# RGB_LED.net
KiCad netlist of a schematic drawn in Altium Designer
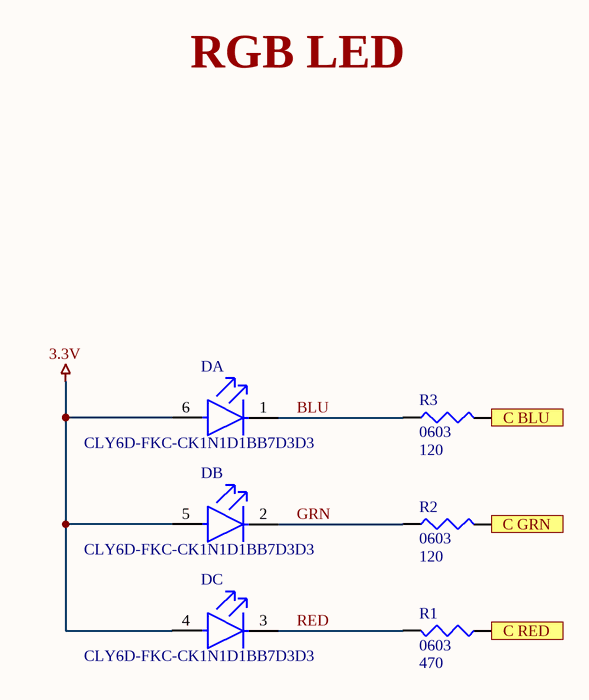
[diagram p0: RGB LED.SchDoc]

(export (version "E")
  (design (tool "Eeschema 10.0.6"))
  (components
    (comp (ref "D")
      (value "CLY6D-FKC-CK1N1D1BB7D3D3")
      (footprint "FP-CLY6D-FKC-MFG")
      (description "LED RGB DIFFUSED 6PLCC SMD")
      (libsource (lib "Altium Content Vault") (part "675964bc96c2f6a68928e7004de3fc3"))
    )
    (comp (ref "R1")
      (value "0603")
      (footprint "J1-0603")
      (description "Resistor")
      (fields (field (name "ALTIUM_VALUE") "470") (field (name "PUBLISHER") "Altium Limited"))
      (libsource (lib "Miscellaneous Devices") (part "Res3"))
    )
    (comp (ref "R2")
      (value "0603")
      (footprint "J1-0603")
      (description "Resistor")
      (fields (field (name "ALTIUM_VALUE") "120") (field (name "PUBLISHER") "Altium Limited"))
      (libsource (lib "Miscellaneous Devices") (part "Res3"))
    )
    (comp (ref "R3")
      (value "0603")
      (footprint "J1-0603")
      (description "Resistor")
      (fields (field (name "ALTIUM_VALUE") "120") (field (name "PUBLISHER") "Altium Limited"))
      (libsource (lib "Miscellaneous Devices") (part "Res3"))
    )
  )
  (nets
    (net (code "1") (name "/BLU") (class "Default")
      (node (ref "D") (pin "1") (pinfunction "BLUE(C)_1") (pintype "passive"))
      (node (ref "R3") (pin "1") (pinfunction "1_1") (pintype "passive"))
    )
    (net (code "2") (name "/C BLU") (class "Default")
      (node (ref "R3") (pin "2") (pinfunction "2_2") (pintype "passive"))
    )
    (net (code "3") (name "/C GRN") (class "Default")
      (node (ref "R2") (pin "2") (pinfunction "2_2") (pintype "passive"))
    )
    (net (code "4") (name "/C RED") (class "Default")
      (node (ref "R1") (pin "1") (pinfunction "1_1") (pintype "passive"))
    )
    (net (code "5") (name "/GRN") (class "Default")
      (node (ref "D") (pin "2") (pinfunction "GREEN(C)_2") (pintype "passive"))
      (node (ref "R2") (pin "1") (pinfunction "1_1") (pintype "passive"))
    )
    (net (code "6") (name "/RED") (class "Default")
      (node (ref "D") (pin "3") (pinfunction "RED(C)_3") (pintype "passive"))
      (node (ref "R1") (pin "2") (pinfunction "2_2") (pintype "passive"))
    )
    (net (code "7") (name "3.3V") (class "Default")
      (node (ref "D") (pin "4") (pinfunction "RED(A)_4") (pintype "passive"))
      (node (ref "D") (pin "5") (pinfunction "GREEN(A)_5") (pintype "passive"))
      (node (ref "D") (pin "6") (pinfunction "BLUE(A)_6") (pintype "passive"))
    )
  )
)
